# Shield_Amir_EDO_V_0_1.net
KiCad netlist of a schematic drawn in EasyEDA
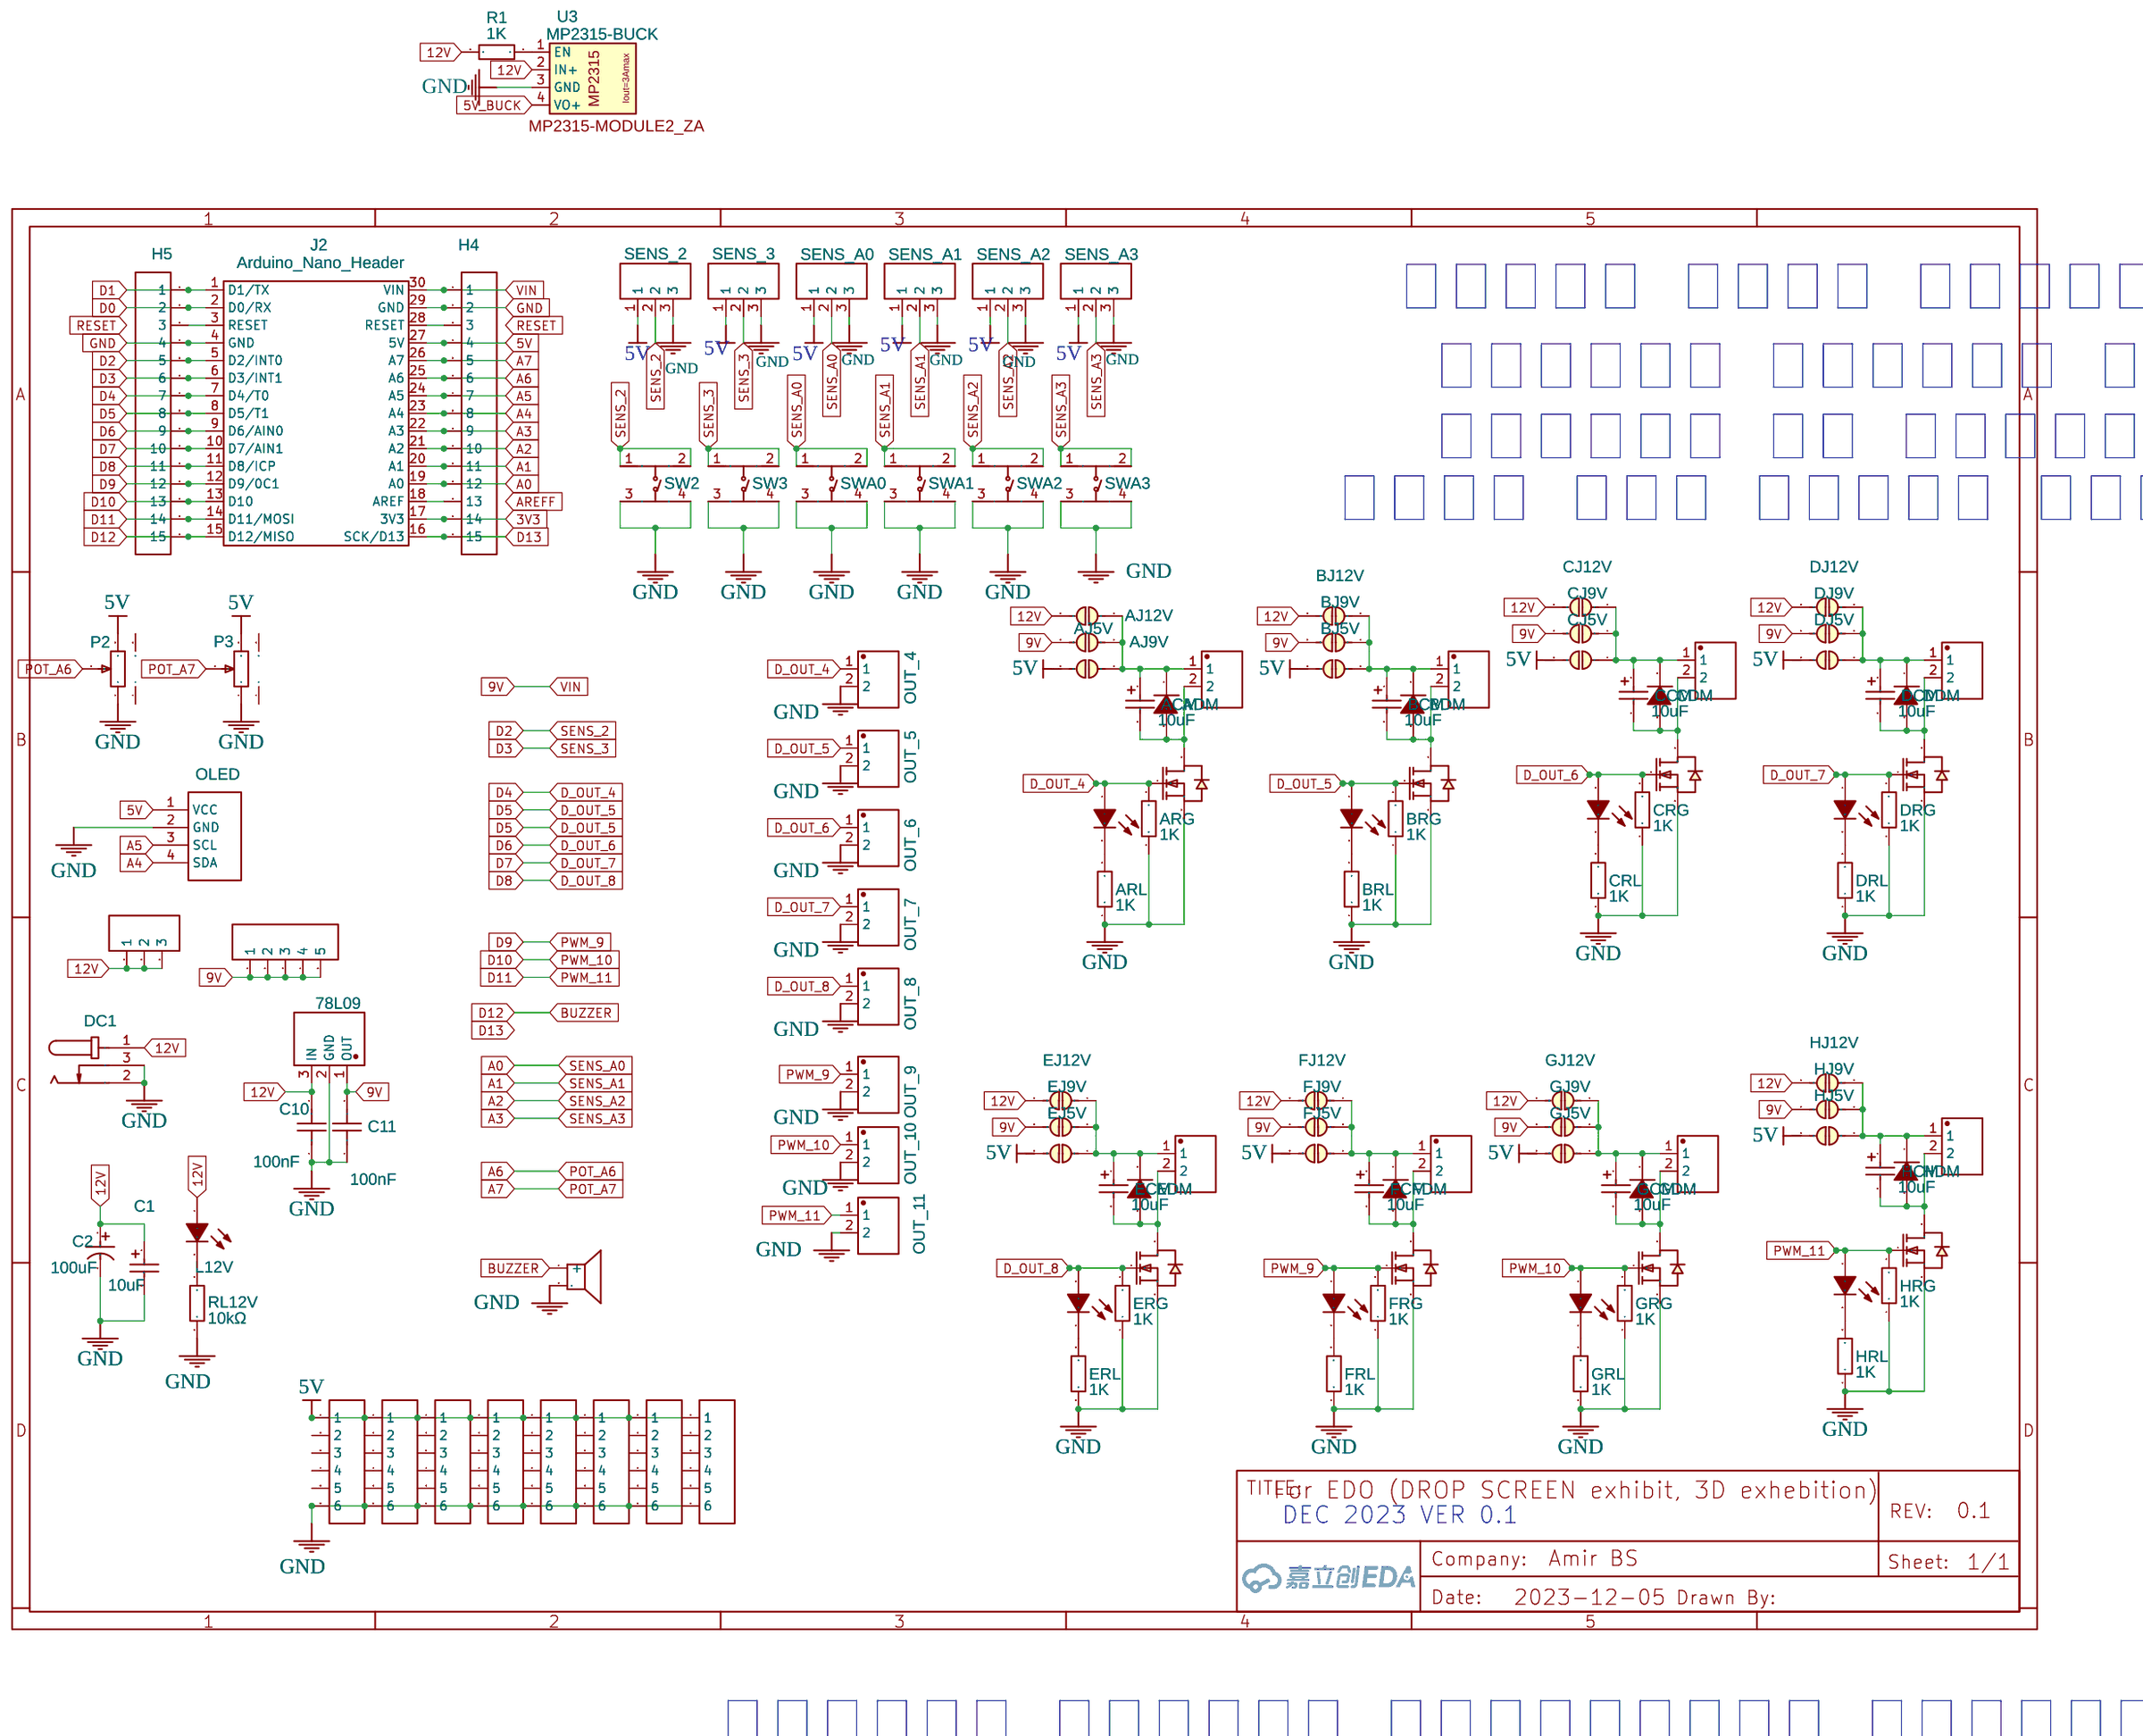
[diagram p0: schematic sheet]

(export (version "E")
  (design (tool "Eeschema 10.0.6"))
  (components
    (comp (ref "ACM")
      (value "10uF")
      (fields (field (name "Manufacturer Part") "TAJA106K016RNJ") (field (name "Manufacturer") "Kyocera AVX"))
      (libsource (lib "") (part "TAJA106K016RNJ_5"))
    )
    (comp (ref "ACON")
      (value "KF2510-2A")
      (fields (field (name "BOM_Supplier Part") "C27543"))
      (libsource (lib "") (part "KF2510-2A_8"))
    )
    (comp (ref "ADM")
      (value "1N4007")
      (fields (field (name "BOM_Manufacturer Part") "1N4007F") (field (name "BOM_Supplier Part") "C110856"))
      (libsource (lib "") (part "1N4007F_5"))
    )
    (comp (ref "AJ5V") (value "JUMPER-SMT_2") (libsource (lib "") (part "JUMPER-SMT_2_16")))
    (comp (ref "AJ9V") (value "JUMPER-SMT_2") (libsource (lib "") (part "JUMPER-SMT_2_12")))
    (comp (ref "AJ12V") (value "JUMPER-SMT_2") (libsource (lib "") (part "JUMPER-SMT_2_10")))
    (comp (ref "ALD")
      (value "LED")
      (fields
        (field (name "BOM_Manufacturer Part") "19-217/BHC-ZL1M2RY/3T")
        (field (name "BOM_Supplier Part") "C72041")
      )
      (libsource (lib "") (part "19-217/BHC-ZL1M2RY/3T_3"))
    )
    (comp (ref "AQ")
      (value "Q")
      (fields (field (name "BOM_Manufacturer Part") "AO3400") (field (name "BOM_Supplier Part") "C5224189"))
      (libsource (lib "") (part "JSM2302"))
    )
    (comp (ref "ARG")
      (value "1K")
      (fields
        (field (name "BOM_Manufacturer Part") "0603WAF1001T5E")
        (field (name "BOM_Supplier Part") "C21190")
      )
      (libsource (lib "") (part "0603WAF1001T5E_10"))
    )
    (comp (ref "ARL")
      (value "1K")
      (fields
        (field (name "BOM_Manufacturer Part") "0603WAF1001T5E")
        (field (name "BOM_Supplier Part") "C21190")
      )
      (libsource (lib "") (part "0603WAF1001T5E_4"))
    )
    (comp (ref "BCM")
      (value "10uF")
      (fields (field (name "Manufacturer Part") "TAJA106K016RNJ") (field (name "Manufacturer") "Kyocera AVX"))
      (libsource (lib "") (part "TAJA106K016RNJ_6"))
    )
    (comp (ref "BCON")
      (value "KF2510-2A")
      (fields (field (name "BOM_Supplier Part") "C27543"))
      (libsource (lib "") (part "KF2510-2A_7"))
    )
    (comp (ref "BDM")
      (value "1N4007")
      (fields (field (name "BOM_Manufacturer Part") "1N4007F") (field (name "BOM_Supplier Part") "C110856"))
      (libsource (lib "") (part "1N4007F"))
    )
    (comp (ref "BJ5V") (value "JUMPER-SMT_2") (libsource (lib "") (part "JUMPER-SMT_2_3")))
    (comp (ref "BJ9V") (value "JUMPER-SMT_2") (libsource (lib "") (part "JUMPER-SMT_2")))
    (comp (ref "BJ12V") (value "JUMPER-SMT_2") (libsource (lib "") (part "JUMPER-SMT_2_7")))
    (comp (ref "BLD")
      (value "LED")
      (fields
        (field (name "BOM_Manufacturer Part") "19-217/BHC-ZL1M2RY/3T")
        (field (name "BOM_Supplier Part") "C72041")
      )
      (libsource (lib "") (part "19-217/BHC-ZL1M2RY/3T_1"))
    )
    (comp (ref "BQ")
      (value "Q")
      (fields (field (name "BOM_Manufacturer Part") "AO3400") (field (name "BOM_Supplier Part") "C5224189"))
      (libsource (lib "") (part "JSM2302_4"))
    )
    (comp (ref "BRG")
      (value "1K")
      (fields
        (field (name "BOM_Manufacturer Part") "0603WAF1001T5E")
        (field (name "BOM_Supplier Part") "C21190")
      )
      (libsource (lib "") (part "0603WAF1001T5E_2"))
    )
    (comp (ref "BRL")
      (value "1K")
      (fields
        (field (name "BOM_Manufacturer Part") "0603WAF1001T5E")
        (field (name "BOM_Supplier Part") "C21190")
      )
      (libsource (lib "") (part "0603WAF1001T5E_13"))
    )
    (comp (ref "BUZZER1")
      (value "BUZZER-12X9")
      (fields (field (name "Manufacturer Part") "buzzer-12X9"))
      (libsource (lib "") (part "BUZZER-12X9"))
    )
    (comp (ref "C1")
      (value "10uF")
      (fields (field (name "Manufacturer Part") "TAJA106K016RNJ") (field (name "Manufacturer") "Kyocera AVX"))
      (libsource (lib "") (part "TAJA106K016RNJ_8"))
    )
    (comp (ref "C2")
      (value "100uF")
      (fields
        (field (name "Manufacturer Part") "KM107M035E11RR0VH2FP0")
        (field (name "Manufacturer") "CX(承兴)")
      )
      (libsource (lib "") (part "100uF 35V 6.3*11"))
    )
    (comp (ref "C10")
      (value "100nF")
      (fields
        (field (name "Manufacturer Part") "CC0603KRX7R9BB104")
        (field (name "Manufacturer") "YAGEO(国巨)")
      )
      (libsource (lib "") (part "CC0603KRX7R9BB104"))
    )
    (comp (ref "C11")
      (value "100nF")
      (fields
        (field (name "Manufacturer Part") "CC0603KRX7R9BB104")
        (field (name "Manufacturer") "YAGEO(国巨)")
      )
      (libsource (lib "") (part "CC0603KRX7R9BB104"))
    )
    (comp (ref "CCM")
      (value "10uF")
      (fields (field (name "Manufacturer Part") "TAJA106K016RNJ") (field (name "Manufacturer") "Kyocera AVX"))
      (libsource (lib "") (part "TAJA106K016RNJ_4"))
    )
    (comp (ref "CCON")
      (value "KF2510-2A")
      (fields (field (name "BOM_Supplier Part") "C27543"))
      (libsource (lib "") (part "KF2510-2A_3"))
    )
    (comp (ref "CDM")
      (value "1N4007")
      (fields (field (name "BOM_Manufacturer Part") "1N4007F") (field (name "BOM_Supplier Part") "C110856"))
      (libsource (lib "") (part "1N4007F_2"))
    )
    (comp (ref "CJ5V") (value "JUMPER-SMT_2") (libsource (lib "") (part "JUMPER-SMT_2_23")))
    (comp (ref "CJ9V") (value "JUMPER-SMT_2") (libsource (lib "") (part "JUMPER-SMT_2_20")))
    (comp (ref "CJ12V") (value "JUMPER-SMT_2") (libsource (lib "") (part "JUMPER-SMT_2_6")))
    (comp (ref "CLD")
      (value "LED")
      (fields
        (field (name "BOM_Manufacturer Part") "19-217/BHC-ZL1M2RY/3T")
        (field (name "BOM_Supplier Part") "C72041")
      )
      (libsource (lib "") (part "19-217/BHC-ZL1M2RY/3T_4"))
    )
    (comp (ref "CQ")
      (value "Q")
      (fields (field (name "BOM_Manufacturer Part") "AO3400") (field (name "BOM_Supplier Part") "C5224189"))
      (libsource (lib "") (part "JSM2302_3"))
    )
    (comp (ref "CRG")
      (value "1K")
      (fields
        (field (name "BOM_Manufacturer Part") "0603WAF1001T5E")
        (field (name "BOM_Supplier Part") "C21190")
      )
      (libsource (lib "") (part "0603WAF1001T5E_14"))
    )
    (comp (ref "CRL")
      (value "1K")
      (fields
        (field (name "BOM_Manufacturer Part") "0603WAF1001T5E")
        (field (name "BOM_Supplier Part") "C21190")
      )
      (libsource (lib "") (part "0603WAF1001T5E_16"))
    )
    (comp (ref "DC1")
      (value "DC")
      (fields
        (field (name "BOM_Manufacturer Part") "DC005-2.0MM")
        (field (name "BOM_Supplier Part") "C111567")
      )
      (libsource (lib "") (part "DC005-2.0MM"))
    )
    (comp (ref "DCM")
      (value "10uF")
      (fields (field (name "Manufacturer Part") "TAJA106K016RNJ") (field (name "Manufacturer") "Kyocera AVX"))
      (libsource (lib "") (part "TAJA106K016RNJ_7"))
    )
    (comp (ref "DCON")
      (value "KF2510-2A")
      (fields (field (name "BOM_Supplier Part") "C27543"))
      (libsource (lib "") (part "KF2510-2A_4"))
    )
    (comp (ref "DDM")
      (value "1N4007")
      (fields (field (name "BOM_Manufacturer Part") "1N4007F") (field (name "BOM_Supplier Part") "C110856"))
      (libsource (lib "") (part "1N4007F_7"))
    )
    (comp (ref "DJ5V") (value "JUMPER-SMT_2") (libsource (lib "") (part "JUMPER-SMT_2_21")))
    (comp (ref "DJ9V") (value "JUMPER-SMT_2") (libsource (lib "") (part "JUMPER-SMT_2_4")))
    (comp (ref "DJ12V") (value "JUMPER-SMT_2") (libsource (lib "") (part "JUMPER-SMT_2_5")))
    (comp (ref "DLD")
      (value "LED")
      (fields
        (field (name "BOM_Manufacturer Part") "19-217/BHC-ZL1M2RY/3T")
        (field (name "BOM_Supplier Part") "C72041")
      )
      (libsource (lib "") (part "19-217/BHC-ZL1M2RY/3T_7"))
    )
    (comp (ref "DQ")
      (value "Q")
      (fields (field (name "BOM_Manufacturer Part") "AO3400") (field (name "BOM_Supplier Part") "C5224189"))
      (libsource (lib "") (part "JSM2302_6"))
    )
    (comp (ref "DRG")
      (value "1K")
      (fields
        (field (name "BOM_Manufacturer Part") "0603WAF1001T5E")
        (field (name "BOM_Supplier Part") "C21190")
      )
      (libsource (lib "") (part "0603WAF1001T5E_15"))
    )
    (comp (ref "DRL")
      (value "1K")
      (fields
        (field (name "BOM_Manufacturer Part") "0603WAF1001T5E")
        (field (name "BOM_Supplier Part") "C21190")
      )
      (libsource (lib "") (part "0603WAF1001T5E_12"))
    )
    (comp (ref "ECM")
      (value "10uF")
      (fields (field (name "Manufacturer Part") "TAJA106K016RNJ") (field (name "Manufacturer") "Kyocera AVX"))
      (libsource (lib "") (part "TAJA106K016RNJ_3"))
    )
    (comp (ref "ECON")
      (value "KF2510-2A")
      (fields (field (name "BOM_Supplier Part") "C27543"))
      (libsource (lib "") (part "KF2510-2A_2"))
    )
    (comp (ref "EDM")
      (value "1N4007")
      (fields (field (name "BOM_Manufacturer Part") "1N4007F") (field (name "BOM_Supplier Part") "C110856"))
      (libsource (lib "") (part "1N4007F_6"))
    )
    (comp (ref "EJ5V") (value "JUMPER-SMT_2") (libsource (lib "") (part "JUMPER-SMT_2_9")))
    (comp (ref "EJ9V") (value "JUMPER-SMT_2") (libsource (lib "") (part "JUMPER-SMT_2_11")))
    (comp (ref "EJ12V") (value "JUMPER-SMT_2") (libsource (lib "") (part "JUMPER-SMT_2_15")))
    (comp (ref "ELD")
      (value "LED")
      (fields
        (field (name "BOM_Manufacturer Part") "19-217/BHC-ZL1M2RY/3T")
        (field (name "BOM_Supplier Part") "C72041")
      )
      (libsource (lib "") (part "19-217/BHC-ZL1M2RY/3T"))
    )
    (comp (ref "EQ")
      (value "Q")
      (fields (field (name "BOM_Manufacturer Part") "AO3400") (field (name "BOM_Supplier Part") "C5224189"))
      (libsource (lib "") (part "JSM2302_2"))
    )
    (comp (ref "ERG")
      (value "1K")
      (fields
        (field (name "BOM_Manufacturer Part") "0603WAF1001T5E")
        (field (name "BOM_Supplier Part") "C21190")
      )
      (libsource (lib "") (part "0603WAF1001T5E_3"))
    )
    (comp (ref "ERL")
      (value "1K")
      (fields
        (field (name "BOM_Manufacturer Part") "0603WAF1001T5E")
        (field (name "BOM_Supplier Part") "C21190")
      )
      (libsource (lib "") (part "0603WAF1001T5E_8"))
    )
    (comp (ref "FCM")
      (value "10uF")
      (fields (field (name "Manufacturer Part") "TAJA106K016RNJ") (field (name "Manufacturer") "Kyocera AVX"))
      (libsource (lib "") (part "TAJA106K016RNJ_1"))
    )
    (comp (ref "FCON")
      (value "KF2510-2A")
      (fields (field (name "BOM_Supplier Part") "C27543"))
      (libsource (lib "") (part "KF2510-2A"))
    )
    (comp (ref "FDM")
      (value "1N4007")
      (fields (field (name "BOM_Manufacturer Part") "1N4007F") (field (name "BOM_Supplier Part") "C110856"))
      (libsource (lib "") (part "1N4007F_1"))
    )
    (comp (ref "FJ5V") (value "JUMPER-SMT_2") (libsource (lib "") (part "JUMPER-SMT_2_17")))
    (comp (ref "FJ9V") (value "JUMPER-SMT_2") (libsource (lib "") (part "JUMPER-SMT_2_14")))
    (comp (ref "FJ12V") (value "JUMPER-SMT_2") (libsource (lib "") (part "JUMPER-SMT_2_18")))
    (comp (ref "FLD")
      (value "LED")
      (fields
        (field (name "BOM_Manufacturer Part") "19-217/BHC-ZL1M2RY/3T")
        (field (name "BOM_Supplier Part") "C72041")
      )
      (libsource (lib "") (part "19-217/BHC-ZL1M2RY/3T_2"))
    )
    (comp (ref "FQ")
      (value "Q")
      (fields (field (name "BOM_Manufacturer Part") "AO3400") (field (name "BOM_Supplier Part") "C5224189"))
      (libsource (lib "") (part "JSM2302_7"))
    )
    (comp (ref "FRG")
      (value "1K")
      (fields
        (field (name "BOM_Manufacturer Part") "0603WAF1001T5E")
        (field (name "BOM_Supplier Part") "C21190")
      )
      (libsource (lib "") (part "0603WAF1001T5E_11"))
    )
    (comp (ref "FRL")
      (value "1K")
      (fields
        (field (name "BOM_Manufacturer Part") "0603WAF1001T5E")
        (field (name "BOM_Supplier Part") "C21190")
      )
      (libsource (lib "") (part "0603WAF1001T5E_9"))
    )
    (comp (ref "GCM")
      (value "10uF")
      (fields (field (name "Manufacturer Part") "TAJA106K016RNJ") (field (name "Manufacturer") "Kyocera AVX"))
      (libsource (lib "") (part "TAJA106K016RNJ"))
    )
    (comp (ref "GCON")
      (value "KF2510-2A")
      (fields (field (name "BOM_Supplier Part") "C27543"))
      (libsource (lib "") (part "KF2510-2A_5"))
    )
    (comp (ref "GDM")
      (value "1N4007")
      (fields (field (name "BOM_Manufacturer Part") "1N4007F") (field (name "BOM_Supplier Part") "C110856"))
      (libsource (lib "") (part "1N4007F_4"))
    )
    (comp (ref "GJ5V") (value "JUMPER-SMT_2") (libsource (lib "") (part "JUMPER-SMT_2_19")))
    (comp (ref "GJ9V") (value "JUMPER-SMT_2") (libsource (lib "") (part "JUMPER-SMT_2_22")))
    (comp (ref "GJ12V") (value "JUMPER-SMT_2") (libsource (lib "") (part "JUMPER-SMT_2_1")))
    (comp (ref "GLD")
      (value "LED")
      (fields
        (field (name "BOM_Manufacturer Part") "19-217/BHC-ZL1M2RY/3T")
        (field (name "BOM_Supplier Part") "C72041")
      )
      (libsource (lib "") (part "19-217/BHC-ZL1M2RY/3T_8"))
    )
    (comp (ref "GQ")
      (value "Q")
      (fields (field (name "BOM_Manufacturer Part") "AO3400") (field (name "BOM_Supplier Part") "C5224189"))
      (libsource (lib "") (part "JSM2302_1"))
    )
    (comp (ref "GRG")
      (value "1K")
      (fields
        (field (name "BOM_Manufacturer Part") "0603WAF1001T5E")
        (field (name "BOM_Supplier Part") "C21190")
      )
      (libsource (lib "") (part "0603WAF1001T5E_7"))
    )
    (comp (ref "GRL")
      (value "1K")
      (fields
        (field (name "BOM_Manufacturer Part") "0603WAF1001T5E")
        (field (name "BOM_Supplier Part") "C21190")
      )
      (libsource (lib "") (part "0603WAF1001T5E_6"))
    )
    (comp (ref "H1")
      (value "HDR-F-2.54_1x6")
      (fields (field (name "BOM_Supplier Part") "C40877"))
      (libsource (lib "") (part "HDR-F-2.54_1x6"))
    )
    (comp (ref "H2")
      (value "HDR-F-2.54_1x6")
      (fields (field (name "BOM_Supplier Part") "C40877"))
      (libsource (lib "") (part "HDR-F-2.54_1x6"))
    )
    (comp (ref "H3")
      (value "HDR-F-2.54_1x6")
      (fields (field (name "BOM_Supplier Part") "C40877"))
      (libsource (lib "") (part "HDR-F-2.54_1x6"))
    )
    (comp (ref "H4")
      (value "HDR-F-2.54_1x15")
      (fields (field (name "BOM_Supplier Part") "C124408"))
      (libsource (lib "") (part "HDR-F-2.54_1x15_1"))
    )
    (comp (ref "H5")
      (value "HDR-F-2.54_1x15")
      (fields (field (name "BOM_Supplier Part") "C124408"))
      (libsource (lib "") (part "HDR-F-2.54_1x15"))
    )
    (comp (ref "H6")
      (value "HDR-F-2.54_1x6")
      (fields (field (name "BOM_Supplier Part") "C40877"))
      (libsource (lib "") (part "HDR-F-2.54_1x6"))
    )
    (comp (ref "H8")
      (value "HDR-F-2.54_1x6")
      (fields (field (name "BOM_Supplier Part") "C40877"))
      (libsource (lib "") (part "HDR-F-2.54_1x6"))
    )
    (comp (ref "H9")
      (value "HDR-F-2.54_1x6")
      (fields (field (name "BOM_Supplier Part") "C40877"))
      (libsource (lib "") (part "HDR-F-2.54_1x6"))
    )
    (comp (ref "H9V")
      (value "HDR-F-2.54_1x5")
      (fields (field (name "BOM_Supplier Part") "C50950"))
      (libsource (lib "") (part "HDR-F-2.54_1x5"))
    )
    (comp (ref "H10")
      (value "HDR-F-2.54_1x6")
      (fields (field (name "BOM_Supplier Part") "C40877"))
      (libsource (lib "") (part "HDR-F-2.54_1x6"))
    )
    (comp (ref "H11")
      (value "HDR-F-2.54_1x6")
      (fields (field (name "BOM_Supplier Part") "C40877"))
      (libsource (lib "") (part "HDR-F-2.54_1x6"))
    )
    (comp (ref "H12V")
      (value "HDR-F-2.54_1x3")
      (fields (field (name "BOM_Supplier Part") "C146690"))
      (libsource (lib "") (part "HDR-F-2.54_1x3"))
    )
    (comp (ref "HCM")
      (value "10uF")
      (fields (field (name "Manufacturer Part") "TAJA106K016RNJ") (field (name "Manufacturer") "Kyocera AVX"))
      (libsource (lib "") (part "TAJA106K016RNJ_2"))
    )
    (comp (ref "HCON")
      (value "KF2510-2A")
      (fields (field (name "BOM_Supplier Part") "C27543"))
      (libsource (lib "") (part "KF2510-2A_6"))
    )
    (comp (ref "HDM")
      (value "1N4007")
      (fields (field (name "BOM_Manufacturer Part") "1N4007F") (field (name "BOM_Supplier Part") "C110856"))
      (libsource (lib "") (part "1N4007F_3"))
    )
    (comp (ref "HJ5V") (value "JUMPER-SMT_2") (libsource (lib "") (part "JUMPER-SMT_2_8")))
    (comp (ref "HJ9V") (value "JUMPER-SMT_2") (libsource (lib "") (part "JUMPER-SMT_2_2")))
    (comp (ref "HJ12V") (value "JUMPER-SMT_2") (libsource (lib "") (part "JUMPER-SMT_2_13")))
    (comp (ref "HLD")
      (value "LED")
      (fields
        (field (name "BOM_Manufacturer Part") "19-217/BHC-ZL1M2RY/3T")
        (field (name "BOM_Supplier Part") "C72041")
      )
      (libsource (lib "") (part "19-217/BHC-ZL1M2RY/3T_5"))
    )
    (comp (ref "HQ")
      (value "Q")
      (fields (field (name "BOM_Manufacturer Part") "AO3400") (field (name "BOM_Supplier Part") "C5224189"))
      (libsource (lib "") (part "JSM2302_5"))
    )
    (comp (ref "HRG")
      (value "1K")
      (fields
        (field (name "BOM_Manufacturer Part") "0603WAF1001T5E")
        (field (name "BOM_Supplier Part") "C21190")
      )
      (libsource (lib "") (part "0603WAF1001T5E"))
    )
    (comp (ref "HRL")
      (value "1K")
      (fields
        (field (name "BOM_Manufacturer Part") "0603WAF1001T5E")
        (field (name "BOM_Supplier Part") "C21190")
      )
      (libsource (lib "") (part "0603WAF1001T5E_1"))
    )
    (comp (ref "J2") (value "Arduino_Nano_Header") (libsource (lib "") (part "Arduino_Nano_Header")))
    (comp (ref "L12V")
      (value "LED")
      (fields
        (field (name "BOM_Manufacturer Part") "19-217/BHC-ZL1M2RY/3T")
        (field (name "BOM_Supplier Part") "C72041")
      )
      (libsource (lib "") (part "19-217/BHC-ZL1M2RY/3T_6"))
    )
    (comp (ref "OLED")
      (value "1.3 inch OLED SSH1106 I2C 128x64 copy")
      (libsource (lib "") (part "1.3 inch OLED SSH1106 I2C 128x64 copy"))
    )
    (comp (ref "OUT_4")
      (value "KF2510-2A")
      (fields (field (name "BOM_Supplier Part") "C27543"))
      (libsource (lib "") (part "KF2510-2A_1"))
    )
    (comp (ref "OUT_5")
      (value "KF2510-2A")
      (fields (field (name "BOM_Supplier Part") "C27543"))
      (libsource (lib "") (part "KF2510-2A_1"))
    )
    (comp (ref "OUT_6")
      (value "KF2510-2A")
      (fields (field (name "BOM_Supplier Part") "C27543"))
      (libsource (lib "") (part "KF2510-2A_1"))
    )
    (comp (ref "OUT_7")
      (value "KF2510-2A")
      (fields (field (name "BOM_Supplier Part") "C27543"))
      (libsource (lib "") (part "KF2510-2A_1"))
    )
    (comp (ref "OUT_8")
      (value "KF2510-2A")
      (fields (field (name "BOM_Supplier Part") "C27543"))
      (libsource (lib "") (part "KF2510-2A_1"))
    )
    (comp (ref "OUT_9")
      (value "KF2510-2A")
      (fields (field (name "BOM_Supplier Part") "C27543"))
      (libsource (lib "") (part "KF2510-2A_1"))
    )
    (comp (ref "OUT_10")
      (value "KF2510-2A")
      (fields (field (name "BOM_Supplier Part") "C27543"))
      (libsource (lib "") (part "KF2510-2A_1"))
    )
    (comp (ref "OUT_11")
      (value "KF2510-2A")
      (fields (field (name "BOM_Supplier Part") "C27543"))
      (libsource (lib "") (part "KF2510-2A_1"))
    )
    (comp (ref "P2")
      (value "长柄旋转电位器")
      (fields (field (name "BOM_Supplier Part") "C2874842"))
      (libsource (lib "") (part "长柄旋转电位器"))
    )
    (comp (ref "P3")
      (value "长柄旋转电位器")
      (fields (field (name "BOM_Supplier Part") "C2874842"))
      (libsource (lib "") (part "长柄旋转电位器"))
    )
    (comp (ref "R1")
      (value "1K")
      (fields
        (field (name "BOM_Manufacturer Part") "0603WAF1001T5E")
        (field (name "BOM_Supplier Part") "C21190")
      )
      (libsource (lib "") (part "0603WAF1001T5E_5"))
    )
    (comp (ref "RL12V")
      (value "10kΩ")
      (fields
        (field (name "BOM_Manufacturer Part") "0603WAF1002T5E")
        (field (name "BOM_Supplier Part") "C25804")
      )
      (libsource (lib "") (part "0603WAF1002T5E"))
    )
    (comp (ref "SENS_2")
      (value "FK2510")
      (fields (field (name "Manufacturer Part") "2510-3A") (field (name "Manufacturer") "BOOMELE(博穆精密)"))
      (libsource (lib "") (part "kf2510_3A"))
    )
    (comp (ref "SENS_3")
      (value "FK2510")
      (fields (field (name "Manufacturer Part") "2510-3A") (field (name "Manufacturer") "BOOMELE(博穆精密)"))
      (libsource (lib "") (part "kf2510_3A"))
    )
    (comp (ref "SENS_A0")
      (value "FK2510")
      (fields (field (name "Manufacturer Part") "2510-3A") (field (name "Manufacturer") "BOOMELE(博穆精密)"))
      (libsource (lib "") (part "kf2510_3A_1"))
    )
    (comp (ref "SENS_A1")
      (value "FK2510")
      (fields (field (name "Manufacturer Part") "2510-3A") (field (name "Manufacturer") "BOOMELE(博穆精密)"))
      (libsource (lib "") (part "kf2510_3A_1"))
    )
    (comp (ref "SENS_A2")
      (value "FK2510")
      (fields (field (name "Manufacturer Part") "2510-3A") (field (name "Manufacturer") "BOOMELE(博穆精密)"))
      (libsource (lib "") (part "kf2510_3A_1"))
    )
    (comp (ref "SENS_A3")
      (value "FK2510")
      (fields (field (name "Manufacturer Part") "2510-3A") (field (name "Manufacturer") "BOOMELE(博穆精密)"))
      (libsource (lib "") (part "kf2510_3A_1"))
    )
    (comp (ref "SW2")
      (value "TC-6610-7-160G")
      (fields (field (name "Manufacturer") "HCTL(华灿天禄)"))
      (libsource (lib "") (part "TC-6610-7-160G_1"))
    )
    (comp (ref "SW3")
      (value "TC-6610-7-160G")
      (fields (field (name "Manufacturer") "HCTL(华灿天禄)"))
      (libsource (lib "") (part "TC-6610-7-160G_1"))
    )
    (comp (ref "SWA0")
      (value "TC-6610-7-160G")
      (fields (field (name "Manufacturer") "HCTL(华灿天禄)"))
      (libsource (lib "") (part "TC-6610-7-160G"))
    )
    (comp (ref "SWA1")
      (value "TC-6610-7-160G")
      (fields (field (name "Manufacturer") "HCTL(华灿天禄)"))
      (libsource (lib "") (part "TC-6610-7-160G"))
    )
    (comp (ref "SWA2")
      (value "TC-6610-7-160G")
      (fields (field (name "Manufacturer") "HCTL(华灿天禄)"))
      (libsource (lib "") (part "TC-6610-7-160G"))
    )
    (comp (ref "SWA3")
      (value "TC-6610-7-160G")
      (fields (field (name "Manufacturer") "HCTL(华灿天禄)"))
      (libsource (lib "") (part "TC-6610-7-160G"))
    )
    (comp (ref "U3") (value "MP2315-BUCK") (libsource (lib "") (part "MP2315-BUCK")))
    (comp (ref "U5")
      (value "78L09")
      (fields (field (name "Manufacturer Part") "78L09U 78L09") (field (name "Manufacturer") "CBI(创基)"))
      (libsource (lib "") (part "78L09U 78L09"))
    )
  )
  (nets
    (net (code "1") (name "3V3") (class "Default")
      (node (ref "H4") (pin "14") (pinfunction "14_14") (pintype "unspecified"))
      (node (ref "J2") (pin "17") (pinfunction "3V3_17") (pintype "unspecified"))
    )
    (net (code "2") (name "5V") (class "Default")
      (node (ref "AJ5V") (pin "2") (pinfunction "2_2") (pintype "bidirectional"))
      (node (ref "BJ5V") (pin "2") (pinfunction "2_2") (pintype "bidirectional"))
      (node (ref "CJ5V") (pin "2") (pinfunction "2_2") (pintype "bidirectional"))
      (node (ref "DJ5V") (pin "2") (pinfunction "2_2") (pintype "bidirectional"))
      (node (ref "EJ5V") (pin "2") (pinfunction "2_2") (pintype "bidirectional"))
      (node (ref "FJ5V") (pin "2") (pinfunction "2_2") (pintype "bidirectional"))
      (node (ref "GJ5V") (pin "2") (pinfunction "2_2") (pintype "bidirectional"))
      (node (ref "H1") (pin "1") (pinfunction "1_1") (pintype "input"))
      (node (ref "H10") (pin "1") (pinfunction "1_1") (pintype "input"))
      (node (ref "H11") (pin "1") (pinfunction "1_1") (pintype "input"))
      (node (ref "H2") (pin "1") (pinfunction "1_1") (pintype "input"))
      (node (ref "H3") (pin "1") (pinfunction "1_1") (pintype "input"))
      (node (ref "H4") (pin "4") (pinfunction "4_4") (pintype "unspecified"))
      (node (ref "H6") (pin "1") (pinfunction "1_1") (pintype "input"))
      (node (ref "H8") (pin "1") (pinfunction "1_1") (pintype "input"))
      (node (ref "H9") (pin "1") (pinfunction "1_1") (pintype "input"))
      (node (ref "HJ5V") (pin "2") (pinfunction "2_2") (pintype "bidirectional"))
      (node (ref "J2") (pin "27") (pinfunction "5V_27") (pintype "unspecified"))
      (node (ref "OLED") (pin "1") (pinfunction "VCC_1") (pintype "passive"))
      (node (ref "P2") (pin "3") (pinfunction "3_3") (pintype "input"))
      (node (ref "P3") (pin "3") (pinfunction "3_3") (pintype "input"))
      (node (ref "SENS_2") (pin "1") (pinfunction "1_1") (pintype "unspecified"))
      (node (ref "SENS_3") (pin "1") (pinfunction "1_1") (pintype "unspecified"))
      (node (ref "SENS_A0") (pin "1") (pinfunction "1_1") (pintype "unspecified"))
      (node (ref "SENS_A1") (pin "1") (pinfunction "1_1") (pintype "unspecified"))
      (node (ref "SENS_A2") (pin "1") (pinfunction "1_1") (pintype "unspecified"))
      (node (ref "SENS_A3") (pin "1") (pinfunction "1_1") (pintype "unspecified"))
    )
    (net (code "3") (name "5V_BUCK") (class "Default")
      (node (ref "U3") (pin "4") (pinfunction "VO+_4") (pintype "unspecified"))
    )
    (net (code "4") (name "9V") (class "Default")
      (node (ref "AJ9V") (pin "2") (pinfunction "2_2") (pintype "bidirectional"))
      (node (ref "BJ9V") (pin "2") (pinfunction "2_2") (pintype "bidirectional"))
      (node (ref "C11") (pin "2") (pinfunction "2_2") (pintype "unspecified"))
      (node (ref "CJ9V") (pin "2") (pinfunction "2_2") (pintype "bidirectional"))
      (node (ref "DJ9V") (pin "2") (pinfunction "2_2") (pintype "bidirectional"))
      (node (ref "EJ9V") (pin "2") (pinfunction "2_2") (pintype "bidirectional"))
      (node (ref "FJ9V") (pin "2") (pinfunction "2_2") (pintype "bidirectional"))
      (node (ref "GJ9V") (pin "2") (pinfunction "2_2") (pintype "bidirectional"))
      (node (ref "H4") (pin "1") (pinfunction "1_1") (pintype "unspecified"))
      (node (ref "H9V") (pin "1") (pinfunction "1_1") (pintype "unspecified"))
      (node (ref "H9V") (pin "2") (pinfunction "2_2") (pintype "unspecified"))
      (node (ref "H9V") (pin "3") (pinfunction "3_3") (pintype "unspecified"))
      (node (ref "H9V") (pin "4") (pinfunction "4_4") (pintype "unspecified"))
      (node (ref "H9V") (pin "5") (pinfunction "5_5") (pintype "unspecified"))
      (node (ref "HJ9V") (pin "2") (pinfunction "2_2") (pintype "bidirectional"))
      (node (ref "J2") (pin "30") (pinfunction "VIN_30") (pintype "unspecified"))
      (node (ref "U5") (pin "1") (pinfunction "OUT_1") (pintype "unspecified"))
    )
    (net (code "5") (name "12V") (class "Default")
      (node (ref "AJ12V") (pin "2") (pinfunction "2_2") (pintype "bidirectional"))
      (node (ref "BJ12V") (pin "2") (pinfunction "2_2") (pintype "bidirectional"))
      (node (ref "C1") (pin "1") (pinfunction "1_1") (pintype "input"))
      (node (ref "C10") (pin "2") (pinfunction "2_2") (pintype "unspecified"))
      (node (ref "C2") (pin "1") (pinfunction "1_1") (pintype "input"))
      (node (ref "CJ12V") (pin "2") (pinfunction "2_2") (pintype "bidirectional"))
      (node (ref "DC1") (pin "1") (pinfunction "1_1") (pintype "unspecified"))
      (node (ref "DJ12V") (pin "2") (pinfunction "2_2") (pintype "bidirectional"))
      (node (ref "EJ12V") (pin "2") (pinfunction "2_2") (pintype "bidirectional"))
      (node (ref "FJ12V") (pin "2") (pinfunction "2_2") (pintype "bidirectional"))
      (node (ref "GJ12V") (pin "2") (pinfunction "2_2") (pintype "bidirectional"))
      (node (ref "H12V") (pin "1") (pinfunction "1_1") (pintype "input"))
      (node (ref "H12V") (pin "2") (pinfunction "2_2") (pintype "input"))
      (node (ref "H12V") (pin "3") (pinfunction "3_3") (pintype "input"))
      (node (ref "HJ12V") (pin "2") (pinfunction "2_2") (pintype "bidirectional"))
      (node (ref "L12V") (pin "1") (pinfunction "A_1") (pintype "input"))
      (node (ref "R1") (pin "2") (pinfunction "2_2") (pintype "input"))
      (node (ref "U3") (pin "2") (pinfunction "IN+_2") (pintype "unspecified"))
      (node (ref "U5") (pin "3") (pinfunction "IN_3") (pintype "unspecified"))
    )
    (net (code "6") (name "A0") (class "Default")
      (node (ref "H4") (pin "12") (pinfunction "12_12") (pintype "unspecified"))
      (node (ref "J2") (pin "19") (pinfunction "A0_19") (pintype "unspecified"))
      (node (ref "SENS_A0") (pin "2") (pinfunction "2_2") (pintype "unspecified"))
      (node (ref "SWA0") (pin "1") (pinfunction "1_1") (pintype "unspecified"))
      (node (ref "SWA0") (pin "2") (pinfunction "2_2") (pintype "unspecified"))
    )
    (net (code "7") (name "A1") (class "Default")
      (node (ref "H4") (pin "11") (pinfunction "11_11") (pintype "unspecified"))
      (node (ref "J2") (pin "20") (pinfunction "A1_20") (pintype "unspecified"))
      (node (ref "SENS_A1") (pin "2") (pinfunction "2_2") (pintype "unspecified"))
      (node (ref "SWA1") (pin "1") (pinfunction "1_1") (pintype "unspecified"))
      (node (ref "SWA1") (pin "2") (pinfunction "2_2") (pintype "unspecified"))
    )
    (net (code "8") (name "A2") (class "Default")
      (node (ref "H4") (pin "10") (pinfunction "10_10") (pintype "unspecified"))
      (node (ref "J2") (pin "21") (pinfunction "A2_21") (pintype "unspecified"))
      (node (ref "SENS_A2") (pin "2") (pinfunction "2_2") (pintype "unspecified"))
      (node (ref "SWA2") (pin "1") (pinfunction "1_1") (pintype "unspecified"))
      (node (ref "SWA2") (pin "2") (pinfunction "2_2") (pintype "unspecified"))
    )
    (net (code "9") (name "A3") (class "Default")
      (node (ref "H4") (pin "9") (pinfunction "9_9") (pintype "unspecified"))
      (node (ref "J2") (pin "22") (pinfunction "A3_22") (pintype "unspecified"))
      (node (ref "SENS_A3") (pin "2") (pinfunction "2_2") (pintype "unspecified"))
      (node (ref "SWA3") (pin "1") (pinfunction "1_1") (pintype "unspecified"))
      (node (ref "SWA3") (pin "2") (pinfunction "2_2") (pintype "unspecified"))
    )
    (net (code "10") (name "A4") (class "Default")
      (node (ref "H4") (pin "8") (pinfunction "8_8") (pintype "unspecified"))
      (node (ref "J2") (pin "23") (pinfunction "A4_23") (pintype "unspecified"))
      (node (ref "OLED") (pin "4") (pinfunction "SDA_4") (pintype "bidirectional"))
    )
    (net (code "11") (name "A5") (class "Default")
      (node (ref "H4") (pin "7") (pinfunction "7_7") (pintype "unspecified"))
      (node (ref "J2") (pin "24") (pinfunction "A5_24") (pintype "unspecified"))
      (node (ref "OLED") (pin "3") (pinfunction "SCL_3") (pintype "bidirectional"))
    )
    (net (code "12") (name "A6") (class "Default")
      (node (ref "H4") (pin "6") (pinfunction "6_6") (pintype "unspecified"))
      (node (ref "J2") (pin "25") (pinfunction "A6_25") (pintype "unspecified"))
      (node (ref "P2") (pin "2") (pinfunction "2_2") (pintype "input"))
    )
    (net (code "13") (name "A7") (class "Default")
      (node (ref "H4") (pin "5") (pinfunction "5_5") (pintype "unspecified"))
      (node (ref "J2") (pin "26") (pinfunction "A7_26") (pintype "unspecified"))
      (node (ref "P3") (pin "2") (pinfunction "2_2") (pintype "input"))
    )
    (net (code "15") (name "BUZZER") (class "Default")
      (node (ref "BUZZER1") (pin "1") (pinfunction "+_1") (pintype "unspecified"))
      (node (ref "H5") (pin "15") (pinfunction "15_15") (pintype "unspecified"))
      (node (ref "J2") (pin "15") (pinfunction "D12/MISO_15") (pintype "unspecified"))
    )
    (net (code "16") (name "D0") (class "Default")
      (node (ref "H5") (pin "2") (pinfunction "2_2") (pintype "unspecified"))
      (node (ref "J2") (pin "2") (pinfunction "D0/RX_2") (pintype "unspecified"))
    )
    (net (code "17") (name "D1") (class "Default")
      (node (ref "H5") (pin "1") (pinfunction "1_1") (pintype "unspecified"))
      (node (ref "J2") (pin "1") (pinfunction "D1/TX_1") (pintype "unspecified"))
    )
    (net (code "18") (name "D2") (class "Default")
      (node (ref "H5") (pin "5") (pinfunction "5_5") (pintype "unspecified"))
      (node (ref "J2") (pin "5") (pinfunction "D2/INT0_5") (pintype "unspecified"))
      (node (ref "SENS_2") (pin "2") (pinfunction "2_2") (pintype "unspecified"))
      (node (ref "SW2") (pin "1") (pinfunction "1_1") (pintype "unspecified"))
      (node (ref "SW2") (pin "2") (pinfunction "2_2") (pintype "unspecified"))
    )
    (net (code "19") (name "D3") (class "Default")
      (node (ref "H5") (pin "6") (pinfunction "6_6") (pintype "unspecified"))
      (node (ref "J2") (pin "6") (pinfunction "D3/INT1_6") (pintype "unspecified"))
      (node (ref "SENS_3") (pin "2") (pinfunction "2_2") (pintype "unspecified"))
      (node (ref "SW3") (pin "1") (pinfunction "1_1") (pintype "unspecified"))
      (node (ref "SW3") (pin "2") (pinfunction "2_2") (pintype "unspecified"))
    )
    (net (code "20") (name "D4") (class "Default")
      (node (ref "ALD") (pin "1") (pinfunction "A_1") (pintype "input"))
      (node (ref "AQ") (pin "1") (pinfunction "G_1") (pintype "unspecified"))
      (node (ref "ARG") (pin "2") (pinfunction "2_2") (pintype "input"))
      (node (ref "H5") (pin "7") (pinfunction "7_7") (pintype "unspecified"))
      (node (ref "J2") (pin "7") (pinfunction "D4/T0_7") (pintype "unspecified"))
      (node (ref "OUT_4") (pin "1") (pinfunction "1_1") (pintype "unspecified"))
    )
    (net (code "21") (name "D5") (class "Default")
      (node (ref "BLD") (pin "1") (pinfunction "A_1") (pintype "input"))
      (node (ref "BQ") (pin "1") (pinfunction "G_1") (pintype "unspecified"))
      (node (ref "BRG") (pin "2") (pinfunction "2_2") (pintype "input"))
      (node (ref "H5") (pin "8") (pinfunction "8_8") (pintype "unspecified"))
      (node (ref "J2") (pin "8") (pinfunction "D5/T1_8") (pintype "unspecified"))
      (node (ref "OUT_5") (pin "1") (pinfunction "1_1") (pintype "unspecified"))
    )
    (net (code "22") (name "D6") (class "Default")
      (node (ref "CLD") (pin "1") (pinfunction "A_1") (pintype "input"))
      (node (ref "CQ") (pin "1") (pinfunction "G_1") (pintype "unspecified"))
      (node (ref "CRG") (pin "2") (pinfunction "2_2") (pintype "input"))
      (node (ref "H5") (pin "9") (pinfunction "9_9") (pintype "unspecified"))
      (node (ref "J2") (pin "9") (pinfunction "D6/AIN0_9") (pintype "unspecified"))
      (node (ref "OUT_6") (pin "1") (pinfunction "1_1") (pintype "unspecified"))
    )
    (net (code "23") (name "D7") (class "Default")
      (node (ref "DLD") (pin "1") (pinfunction "A_1") (pintype "input"))
      (node (ref "DQ") (pin "1") (pinfunction "G_1") (pintype "unspecified"))
      (node (ref "DRG") (pin "2") (pinfunction "2_2") (pintype "input"))
      (node (ref "H5") (pin "10") (pinfunction "10_10") (pintype "unspecified"))
      (node (ref "J2") (pin "10") (pinfunction "D7/AIN1_10") (pintype "unspecified"))
      (node (ref "OUT_7") (pin "1") (pinfunction "1_1") (pintype "unspecified"))
    )
    (net (code "24") (name "D8") (class "Default")
      (node (ref "ELD") (pin "1") (pinfunction "A_1") (pintype "input"))
      (node (ref "EQ") (pin "1") (pinfunction "G_1") (pintype "unspecified"))
      (node (ref "ERG") (pin "2") (pinfunction "2_2") (pintype "input"))
      (node (ref "H5") (pin "11") (pinfunction "11_11") (pintype "unspecified"))
      (node (ref "J2") (pin "11") (pinfunction "D8/ICP_11") (pintype "unspecified"))
      (node (ref "OUT_8") (pin "1") (pinfunction "1_1") (pintype "unspecified"))
    )
    (net (code "25") (name "D9") (class "Default")
      (node (ref "FLD") (pin "1") (pinfunction "A_1") (pintype "input"))
      (node (ref "FQ") (pin "1") (pinfunction "G_1") (pintype "unspecified"))
      (node (ref "FRG") (pin "2") (pinfunction "2_2") (pintype "input"))
      (node (ref "H5") (pin "12") (pinfunction "12_12") (pintype "unspecified"))
      (node (ref "J2") (pin "12") (pinfunction "D9/0C1_12") (pintype "unspecified"))
      (node (ref "OUT_9") (pin "1") (pinfunction "1_1") (pintype "unspecified"))
    )
    (net (code "26") (name "D10") (class "Default")
      (node (ref "GLD") (pin "1") (pinfunction "A_1") (pintype "input"))
      (node (ref "GQ") (pin "1") (pinfunction "G_1") (pintype "unspecified"))
      (node (ref "GRG") (pin "2") (pinfunction "2_2") (pintype "input"))
      (node (ref "H5") (pin "13") (pinfunction "13_13") (pintype "unspecified"))
      (node (ref "J2") (pin "13") (pinfunction "D10_13") (pintype "unspecified"))
      (node (ref "OUT_10") (pin "1") (pinfunction "1_1") (pintype "unspecified"))
    )
    (net (code "27") (name "D11") (class "Default")
      (node (ref "H5") (pin "14") (pinfunction "14_14") (pintype "unspecified"))
      (node (ref "HLD") (pin "1") (pinfunction "A_1") (pintype "input"))
      (node (ref "HQ") (pin "1") (pinfunction "G_1") (pintype "unspecified"))
      (node (ref "HRG") (pin "2") (pinfunction "2_2") (pintype "input"))
      (node (ref "J2") (pin "14") (pinfunction "D11/MOSI_14") (pintype "unspecified"))
      (node (ref "OUT_11") (pin "1") (pinfunction "1_1") (pintype "unspecified"))
    )
    (net (code "28") (name "D13") (class "Default")
      (node (ref "H4") (pin "15") (pinfunction "15_15") (pintype "unspecified"))
      (node (ref "J2") (pin "16") (pinfunction "SCK/D13_16") (pintype "unspecified"))
    )
    (net (code "29") (name "GND") (class "Default")
      (node (ref "AQ") (pin "2") (pinfunction "S_2") (pintype "unspecified"))
      (node (ref "ARG") (pin "1") (pinfunction "1_1") (pintype "input"))
      (node (ref "ARL") (pin "1") (pinfunction "1_1") (pintype "input"))
      (node (ref "BQ") (pin "2") (pinfunction "S_2") (pintype "unspecified"))
      (node (ref "BRG") (pin "1") (pinfunction "1_1") (pintype "input"))
      (node (ref "BRL") (pin "1") (pinfunction "1_1") (pintype "input"))
      (node (ref "BUZZER1") (pin "2") (pinfunction "2_2") (pintype "unspecified"))
      (node (ref "C1") (pin "2") (pinfunction "2_2") (pintype "input"))
      (node (ref "C10") (pin "1") (pinfunction "1_1") (pintype "unspecified"))
      (node (ref "C11") (pin "1") (pinfunction "1_1") (pintype "unspecified"))
      (node (ref "C2") (pin "2") (pinfunction "2_2") (pintype "input"))
      (node (ref "CQ") (pin "2") (pinfunction "S_2") (pintype "unspecified"))
      (node (ref "CRG") (pin "1") (pinfunction "1_1") (pintype "input"))
      (node (ref "CRL") (pin "1") (pinfunction "1_1") (pintype "input"))
      (node (ref "DC1") (pin "2") (pinfunction "2_2") (pintype "unspecified"))
      (node (ref "DC1") (pin "3") (pinfunction "3_3") (pintype "unspecified"))
      (node (ref "DQ") (pin "2") (pinfunction "S_2") (pintype "unspecified"))
      (node (ref "DRG") (pin "1") (pinfunction "1_1") (pintype "input"))
      (node (ref "DRL") (pin "1") (pinfunction "1_1") (pintype "input"))
      (node (ref "EQ") (pin "2") (pinfunction "S_2") (pintype "unspecified"))
      (node (ref "ERG") (pin "1") (pinfunction "1_1") (pintype "input"))
      (node (ref "ERL") (pin "1") (pinfunction "1_1") (pintype "input"))
      (node (ref "FQ") (pin "2") (pinfunction "S_2") (pintype "unspecified"))
      (node (ref "FRG") (pin "1") (pinfunction "1_1") (pintype "input"))
      (node (ref "FRL") (pin "1") (pinfunction "1_1") (pintype "input"))
      (node (ref "GQ") (pin "2") (pinfunction "S_2") (pintype "unspecified"))
      (node (ref "GRG") (pin "1") (pinfunction "1_1") (pintype "input"))
      (node (ref "GRL") (pin "1") (pinfunction "1_1") (pintype "input"))
      (node (ref "H1") (pin "6") (pinfunction "6_6") (pintype "input"))
      (node (ref "H10") (pin "6") (pinfunction "6_6") (pintype "input"))
      (node (ref "H11") (pin "6") (pinfunction "6_6") (pintype "input"))
      (node (ref "H2") (pin "6") (pinfunction "6_6") (pintype "input"))
      (node (ref "H3") (pin "6") (pinfunction "6_6") (pintype "input"))
      (node (ref "H4") (pin "2") (pinfunction "2_2") (pintype "unspecified"))
      (node (ref "H5") (pin "4") (pinfunction "4_4") (pintype "unspecified"))
      (node (ref "H6") (pin "6") (pinfunction "6_6") (pintype "input"))
      (node (ref "H8") (pin "6") (pinfunction "6_6") (pintype "input"))
      (node (ref "H9") (pin "6") (pinfunction "6_6") (pintype "input"))
      (node (ref "HQ") (pin "2") (pinfunction "S_2") (pintype "unspecified"))
      (node (ref "HRG") (pin "1") (pinfunction "1_1") (pintype "input"))
      (node (ref "HRL") (pin "1") (pinfunction "1_1") (pintype "input"))
      (node (ref "J2") (pin "29") (pinfunction "GND_29") (pintype "unspecified"))
      (node (ref "J2") (pin "4") (pinfunction "GND_4") (pintype "unspecified"))
      (node (ref "OLED") (pin "2") (pinfunction "GND_2") (pintype "passive"))
      (node (ref "OUT_10") (pin "2") (pinfunction "2_2") (pintype "unspecified"))
      (node (ref "OUT_11") (pin "2") (pinfunction "2_2") (pintype "unspecified"))
      (node (ref "OUT_4") (pin "2") (pinfunction "2_2") (pintype "unspecified"))
      (node (ref "OUT_5") (pin "2") (pinfunction "2_2") (pintype "unspecified"))
      (node (ref "OUT_6") (pin "2") (pinfunction "2_2") (pintype "unspecified"))
      (node (ref "OUT_7") (pin "2") (pinfunction "2_2") (pintype "unspecified"))
      (node (ref "OUT_8") (pin "2") (pinfunction "2_2") (pintype "unspecified"))
      (node (ref "OUT_9") (pin "2") (pinfunction "2_2") (pintype "unspecified"))
      (node (ref "P2") (pin "1") (pinfunction "1_1") (pintype "input"))
      (node (ref "P3") (pin "1") (pinfunction "1_1") (pintype "input"))
      (node (ref "RL12V") (pin "2") (pinfunction "2_2") (pintype "input"))
      (node (ref "SENS_2") (pin "3") (pinfunction "3_3") (pintype "unspecified"))
      (node (ref "SENS_3") (pin "3") (pinfunction "3_3") (pintype "unspecified"))
      (node (ref "SENS_A0") (pin "3") (pinfunction "3_3") (pintype "unspecified"))
      (node (ref "SENS_A1") (pin "3") (pinfunction "3_3") (pintype "unspecified"))
      (node (ref "SENS_A2") (pin "3") (pinfunction "3_3") (pintype "unspecified"))
      (node (ref "SENS_A3") (pin "3") (pinfunction "3_3") (pintype "unspecified"))
      (node (ref "SW2") (pin "3") (pinfunction "3_3") (pintype "unspecified"))
      (node (ref "SW2") (pin "4") (pinfunction "4_4") (pintype "unspecified"))
      (node (ref "SW3") (pin "3") (pinfunction "3_3") (pintype "unspecified"))
      (node (ref "SW3") (pin "4") (pinfunction "4_4") (pintype "unspecified"))
      (node (ref "SWA0") (pin "3") (pinfunction "3_3") (pintype "unspecified"))
      (node (ref "SWA0") (pin "4") (pinfunction "4_4") (pintype "unspecified"))
      (node (ref "SWA1") (pin "3") (pinfunction "3_3") (pintype "unspecified"))
      (node (ref "SWA1") (pin "4") (pinfunction "4_4") (pintype "unspecified"))
      (node (ref "SWA2") (pin "3") (pinfunction "3_3") (pintype "unspecified"))
      (node (ref "SWA2") (pin "4") (pinfunction "4_4") (pintype "unspecified"))
      (node (ref "SWA3") (pin "3") (pinfunction "3_3") (pintype "unspecified"))
      (node (ref "SWA3") (pin "4") (pinfunction "4_4") (pintype "unspecified"))
      (node (ref "U3") (pin "3") (pinfunction "GND_3") (pintype "unspecified"))
      (node (ref "U5") (pin "2") (pinfunction "GND_2") (pintype "unspecified"))
    )
    (net (code "30") (name "Net-(ADM-A)") (class "Default")
      (node (ref "ACM") (pin "2") (pinfunction "2_2") (pintype "input"))
      (node (ref "ACON") (pin "2") (pinfunction "2_2") (pintype "unspecified"))
      (node (ref "ADM") (pin "2") (pinfunction "A_2") (pintype "unspecified"))
      (node (ref "AQ") (pin "3") (pinfunction "D_3") (pintype "unspecified"))
    )
    (net (code "31") (name "Net-(ADM-C)") (class "Default")
      (node (ref "ACM") (pin "1") (pinfunction "1_1") (pintype "input"))
      (node (ref "ACON") (pin "1") (pinfunction "1_1") (pintype "unspecified"))
      (node (ref "ADM") (pin "1") (pinfunction "C_1") (pintype "unspecified"))
      (node (ref "AJ12V") (pin "1") (pinfunction "1_1") (pintype "bidirectional"))
      (node (ref "AJ5V") (pin "1") (pinfunction "1_1") (pintype "bidirectional"))
      (node (ref "AJ9V") (pin "1") (pinfunction "1_1") (pintype "bidirectional"))
    )
    (net (code "32") (name "Net-(ALD-C)") (class "Default")
      (node (ref "ALD") (pin "2") (pinfunction "C_2") (pintype "input"))
      (node (ref "ARL") (pin "2") (pinfunction "2_2") (pintype "input"))
    )
    (net (code "33") (name "Net-(BDM-A)") (class "Default")
      (node (ref "BCM") (pin "2") (pinfunction "2_2") (pintype "input"))
      (node (ref "BCON") (pin "2") (pinfunction "2_2") (pintype "unspecified"))
      (node (ref "BDM") (pin "2") (pinfunction "A_2") (pintype "unspecified"))
      (node (ref "BQ") (pin "3") (pinfunction "D_3") (pintype "unspecified"))
    )
    (net (code "34") (name "Net-(BDM-C)") (class "Default")
      (node (ref "BCM") (pin "1") (pinfunction "1_1") (pintype "input"))
      (node (ref "BCON") (pin "1") (pinfunction "1_1") (pintype "unspecified"))
      (node (ref "BDM") (pin "1") (pinfunction "C_1") (pintype "unspecified"))
      (node (ref "BJ12V") (pin "1") (pinfunction "1_1") (pintype "bidirectional"))
      (node (ref "BJ5V") (pin "1") (pinfunction "1_1") (pintype "bidirectional"))
      (node (ref "BJ9V") (pin "1") (pinfunction "1_1") (pintype "bidirectional"))
    )
    (net (code "35") (name "Net-(BLD-C)") (class "Default")
      (node (ref "BLD") (pin "2") (pinfunction "C_2") (pintype "input"))
      (node (ref "BRL") (pin "2") (pinfunction "2_2") (pintype "input"))
    )
    (net (code "36") (name "Net-(CDM-A)") (class "Default")
      (node (ref "CCM") (pin "2") (pinfunction "2_2") (pintype "input"))
      (node (ref "CCON") (pin "2") (pinfunction "2_2") (pintype "unspecified"))
      (node (ref "CDM") (pin "2") (pinfunction "A_2") (pintype "unspecified"))
      (node (ref "CQ") (pin "3") (pinfunction "D_3") (pintype "unspecified"))
    )
    (net (code "37") (name "Net-(CDM-C)") (class "Default")
      (node (ref "CCM") (pin "1") (pinfunction "1_1") (pintype "input"))
      (node (ref "CCON") (pin "1") (pinfunction "1_1") (pintype "unspecified"))
      (node (ref "CDM") (pin "1") (pinfunction "C_1") (pintype "unspecified"))
      (node (ref "CJ12V") (pin "1") (pinfunction "1_1") (pintype "bidirectional"))
      (node (ref "CJ5V") (pin "1") (pinfunction "1_1") (pintype "bidirectional"))
      (node (ref "CJ9V") (pin "1") (pinfunction "1_1") (pintype "bidirectional"))
    )
    (net (code "38") (name "Net-(CLD-C)") (class "Default")
      (node (ref "CLD") (pin "2") (pinfunction "C_2") (pintype "input"))
      (node (ref "CRL") (pin "2") (pinfunction "2_2") (pintype "input"))
    )
    (net (code "39") (name "Net-(DDM-A)") (class "Default")
      (node (ref "DCM") (pin "2") (pinfunction "2_2") (pintype "input"))
      (node (ref "DCON") (pin "2") (pinfunction "2_2") (pintype "unspecified"))
      (node (ref "DDM") (pin "2") (pinfunction "A_2") (pintype "unspecified"))
      (node (ref "DQ") (pin "3") (pinfunction "D_3") (pintype "unspecified"))
    )
    (net (code "40") (name "Net-(DDM-C)") (class "Default")
      (node (ref "DCM") (pin "1") (pinfunction "1_1") (pintype "input"))
      (node (ref "DCON") (pin "1") (pinfunction "1_1") (pintype "unspecified"))
      (node (ref "DDM") (pin "1") (pinfunction "C_1") (pintype "unspecified"))
      (node (ref "DJ12V") (pin "1") (pinfunction "1_1") (pintype "bidirectional"))
      (node (ref "DJ5V") (pin "1") (pinfunction "1_1") (pintype "bidirectional"))
      (node (ref "DJ9V") (pin "1") (pinfunction "1_1") (pintype "bidirectional"))
    )
    (net (code "41") (name "Net-(DLD-C)") (class "Default")
      (node (ref "DLD") (pin "2") (pinfunction "C_2") (pintype "input"))
      (node (ref "DRL") (pin "2") (pinfunction "2_2") (pintype "input"))
    )
    (net (code "42") (name "Net-(EDM-A)") (class "Default")
      (node (ref "ECM") (pin "2") (pinfunction "2_2") (pintype "input"))
      (node (ref "ECON") (pin "2") (pinfunction "2_2") (pintype "unspecified"))
      (node (ref "EDM") (pin "2") (pinfunction "A_2") (pintype "unspecified"))
      (node (ref "EQ") (pin "3") (pinfunction "D_3") (pintype "unspecified"))
    )
    (net (code "43") (name "Net-(EDM-C)") (class "Default")
      (node (ref "ECM") (pin "1") (pinfunction "1_1") (pintype "input"))
      (node (ref "ECON") (pin "1") (pinfunction "1_1") (pintype "unspecified"))
      (node (ref "EDM") (pin "1") (pinfunction "C_1") (pintype "unspecified"))
      (node (ref "EJ12V") (pin "1") (pinfunction "1_1") (pintype "bidirectional"))
      (node (ref "EJ5V") (pin "1") (pinfunction "1_1") (pintype "bidirectional"))
      (node (ref "EJ9V") (pin "1") (pinfunction "1_1") (pintype "bidirectional"))
    )
    (net (code "44") (name "Net-(ELD-C)") (class "Default")
      (node (ref "ELD") (pin "2") (pinfunction "C_2") (pintype "input"))
      (node (ref "ERL") (pin "2") (pinfunction "2_2") (pintype "input"))
    )
    (net (code "45") (name "Net-(FDM-A)") (class "Default")
      (node (ref "FCM") (pin "2") (pinfunction "2_2") (pintype "input"))
      (node (ref "FCON") (pin "2") (pinfunction "2_2") (pintype "unspecified"))
      (node (ref "FDM") (pin "2") (pinfunction "A_2") (pintype "unspecified"))
      (node (ref "FQ") (pin "3") (pinfunction "D_3") (pintype "unspecified"))
    )
    (net (code "46") (name "Net-(FDM-C)") (class "Default")
      (node (ref "FCM") (pin "1") (pinfunction "1_1") (pintype "input"))
      (node (ref "FCON") (pin "1") (pinfunction "1_1") (pintype "unspecified"))
      (node (ref "FDM") (pin "1") (pinfunction "C_1") (pintype "unspecified"))
      (node (ref "FJ12V") (pin "1") (pinfunction "1_1") (pintype "bidirectional"))
      (node (ref "FJ5V") (pin "1") (pinfunction "1_1") (pintype "bidirectional"))
      (node (ref "FJ9V") (pin "1") (pinfunction "1_1") (pintype "bidirectional"))
    )
    (net (code "47") (name "Net-(FLD-C)") (class "Default")
      (node (ref "FLD") (pin "2") (pinfunction "C_2") (pintype "input"))
      (node (ref "FRL") (pin "2") (pinfunction "2_2") (pintype "input"))
    )
    (net (code "48") (name "Net-(GDM-A)") (class "Default")
      (node (ref "GCM") (pin "2") (pinfunction "2_2") (pintype "input"))
      (node (ref "GCON") (pin "2") (pinfunction "2_2") (pintype "unspecified"))
      (node (ref "GDM") (pin "2") (pinfunction "A_2") (pintype "unspecified"))
      (node (ref "GQ") (pin "3") (pinfunction "D_3") (pintype "unspecified"))
    )
    (net (code "49") (name "Net-(GDM-C)") (class "Default")
      (node (ref "GCM") (pin "1") (pinfunction "1_1") (pintype "input"))
      (node (ref "GCON") (pin "1") (pinfunction "1_1") (pintype "unspecified"))
      (node (ref "GDM") (pin "1") (pinfunction "C_1") (pintype "unspecified"))
      (node (ref "GJ12V") (pin "1") (pinfunction "1_1") (pintype "bidirectional"))
      (node (ref "GJ5V") (pin "1") (pinfunction "1_1") (pintype "bidirectional"))
      (node (ref "GJ9V") (pin "1") (pinfunction "1_1") (pintype "bidirectional"))
    )
    (net (code "50") (name "Net-(GLD-C)") (class "Default")
      (node (ref "GLD") (pin "2") (pinfunction "C_2") (pintype "input"))
      (node (ref "GRL") (pin "2") (pinfunction "2_2") (pintype "input"))
    )
    (net (code "51") (name "Net-(H4-Pad3)") (class "Default")
      (node (ref "H4") (pin "3") (pinfunction "3_3") (pintype "unspecified"))
      (node (ref "J2") (pin "28") (pinfunction "RESET_28") (pintype "unspecified"))
    )
    (net (code "52") (name "Net-(H5-Pad3)") (class "Default")
      (node (ref "H5") (pin "3") (pinfunction "3_3") (pintype "unspecified"))
      (node (ref "J2") (pin "3") (pinfunction "RESET_3") (pintype "unspecified"))
    )
    (net (code "53") (name "Net-(HDM-A)") (class "Default")
      (node (ref "HCM") (pin "2") (pinfunction "2_2") (pintype "input"))
      (node (ref "HCON") (pin "2") (pinfunction "2_2") (pintype "unspecified"))
      (node (ref "HDM") (pin "2") (pinfunction "A_2") (pintype "unspecified"))
      (node (ref "HQ") (pin "3") (pinfunction "D_3") (pintype "unspecified"))
    )
    (net (code "54") (name "Net-(HDM-C)") (class "Default")
      (node (ref "HCM") (pin "1") (pinfunction "1_1") (pintype "input"))
      (node (ref "HCON") (pin "1") (pinfunction "1_1") (pintype "unspecified"))
      (node (ref "HDM") (pin "1") (pinfunction "C_1") (pintype "unspecified"))
      (node (ref "HJ12V") (pin "1") (pinfunction "1_1") (pintype "bidirectional"))
      (node (ref "HJ5V") (pin "1") (pinfunction "1_1") (pintype "bidirectional"))
      (node (ref "HJ9V") (pin "1") (pinfunction "1_1") (pintype "bidirectional"))
    )
    (net (code "55") (name "Net-(HLD-C)") (class "Default")
      (node (ref "HLD") (pin "2") (pinfunction "C_2") (pintype "input"))
      (node (ref "HRL") (pin "2") (pinfunction "2_2") (pintype "input"))
    )
    (net (code "56") (name "Net-(J2-AREF)") (class "Default")
      (node (ref "H4") (pin "13") (pinfunction "13_13") (pintype "unspecified"))
      (node (ref "J2") (pin "18") (pinfunction "AREF_18") (pintype "unspecified"))
    )
    (net (code "57") (name "Net-(L12V-C)") (class "Default")
      (node (ref "L12V") (pin "2") (pinfunction "C_2") (pintype "input"))
      (node (ref "RL12V") (pin "1") (pinfunction "1_1") (pintype "input"))
    )
    (net (code "58") (name "Net-(U3-EN)") (class "Default")
      (node (ref "R1") (pin "1") (pinfunction "1_1") (pintype "input"))
      (node (ref "U3") (pin "1") (pinfunction "EN_1") (pintype "unspecified"))
    )
    (net (code "60") (name "unconnected-(H1-Pad2)") (class "Default")
      (node (ref "H1") (pin "2") (pinfunction "2_2") (pintype "input"))
    )
    (net (code "61") (name "unconnected-(H1-Pad3)") (class "Default")
      (node (ref "H1") (pin "3") (pinfunction "3_3") (pintype "input"))
    )
    (net (code "62") (name "unconnected-(H1-Pad4)") (class "Default")
      (node (ref "H1") (pin "4") (pinfunction "4_4") (pintype "input"))
    )
    (net (code "63") (name "unconnected-(H1-Pad5)") (class "Default")
      (node (ref "H1") (pin "5") (pinfunction "5_5") (pintype "input"))
    )
    (net (code "64") (name "unconnected-(H2-Pad2)") (class "Default")
      (node (ref "H2") (pin "2") (pinfunction "2_2") (pintype "input"))
    )
    (net (code "65") (name "unconnected-(H2-Pad3)") (class "Default")
      (node (ref "H2") (pin "3") (pinfunction "3_3") (pintype "input"))
    )
    (net (code "66") (name "unconnected-(H2-Pad4)") (class "Default")
      (node (ref "H2") (pin "4") (pinfunction "4_4") (pintype "input"))
    )
    (net (code "67") (name "unconnected-(H2-Pad5)") (class "Default")
      (node (ref "H2") (pin "5") (pinfunction "5_5") (pintype "input"))
    )
    (net (code "68") (name "unconnected-(H3-Pad2)") (class "Default")
      (node (ref "H3") (pin "2") (pinfunction "2_2") (pintype "input"))
    )
    (net (code "69") (name "unconnected-(H3-Pad3)") (class "Default")
      (node (ref "H3") (pin "3") (pinfunction "3_3") (pintype "input"))
    )
    (net (code "70") (name "unconnected-(H3-Pad4)") (class "Default")
      (node (ref "H3") (pin "4") (pinfunction "4_4") (pintype "input"))
    )
    (net (code "71") (name "unconnected-(H3-Pad5)") (class "Default")
      (node (ref "H3") (pin "5") (pinfunction "5_5") (pintype "input"))
    )
    (net (code "72") (name "unconnected-(H6-Pad2)") (class "Default")
      (node (ref "H6") (pin "2") (pinfunction "2_2") (pintype "input"))
    )
    (net (code "73") (name "unconnected-(H6-Pad3)") (class "Default")
      (node (ref "H6") (pin "3") (pinfunction "3_3") (pintype "input"))
    )
    (net (code "74") (name "unconnected-(H6-Pad4)") (class "Default")
      (node (ref "H6") (pin "4") (pinfunction "4_4") (pintype "input"))
    )
    (net (code "75") (name "unconnected-(H6-Pad5)") (class "Default")
      (node (ref "H6") (pin "5") (pinfunction "5_5") (pintype "input"))
    )
    (net (code "76") (name "unconnected-(H8-Pad2)") (class "Default")
      (node (ref "H8") (pin "2") (pinfunction "2_2") (pintype "input"))
    )
    (net (code "77") (name "unconnected-(H8-Pad3)") (class "Default")
      (node (ref "H8") (pin "3") (pinfunction "3_3") (pintype "input"))
    )
    (net (code "78") (name "unconnected-(H8-Pad4)") (class "Default")
      (node (ref "H8") (pin "4") (pinfunction "4_4") (pintype "input"))
    )
    (net (code "79") (name "unconnected-(H8-Pad5)") (class "Default")
      (node (ref "H8") (pin "5") (pinfunction "5_5") (pintype "input"))
    )
    (net (code "80") (name "unconnected-(H9-Pad2)") (class "Default")
      (node (ref "H9") (pin "2") (pinfunction "2_2") (pintype "input"))
    )
    (net (code "81") (name "unconnected-(H9-Pad3)") (class "Default")
      (node (ref "H9") (pin "3") (pinfunction "3_3") (pintype "input"))
    )
    (net (code "82") (name "unconnected-(H9-Pad4)") (class "Default")
      (node (ref "H9") (pin "4") (pinfunction "4_4") (pintype "input"))
    )
    (net (code "83") (name "unconnected-(H9-Pad5)") (class "Default")
      (node (ref "H9") (pin "5") (pinfunction "5_5") (pintype "input"))
    )
    (net (code "84") (name "unconnected-(H10-Pad2)") (class "Default")
      (node (ref "H10") (pin "2") (pinfunction "2_2") (pintype "input"))
    )
    (net (code "85") (name "unconnected-(H10-Pad3)") (class "Default")
      (node (ref "H10") (pin "3") (pinfunction "3_3") (pintype "input"))
    )
    (net (code "86") (name "unconnected-(H10-Pad4)") (class "Default")
      (node (ref "H10") (pin "4") (pinfunction "4_4") (pintype "input"))
    )
    (net (code "87") (name "unconnected-(H10-Pad5)") (class "Default")
      (node (ref "H10") (pin "5") (pinfunction "5_5") (pintype "input"))
    )
    (net (code "88") (name "unconnected-(H11-Pad2)") (class "Default")
      (node (ref "H11") (pin "2") (pinfunction "2_2") (pintype "input"))
    )
    (net (code "89") (name "unconnected-(H11-Pad3)") (class "Default")
      (node (ref "H11") (pin "3") (pinfunction "3_3") (pintype "input"))
    )
    (net (code "90") (name "unconnected-(H11-Pad4)") (class "Default")
      (node (ref "H11") (pin "4") (pinfunction "4_4") (pintype "input"))
    )
    (net (code "91") (name "unconnected-(H11-Pad5)") (class "Default")
      (node (ref "H11") (pin "5") (pinfunction "5_5") (pintype "input"))
    )
    (net (code "92") (name "unconnected-(P2-Pad4)") (class "Default")
      (node (ref "P2") (pin "4") (pinfunction "4_4") (pintype "input"))
    )
    (net (code "93") (name "unconnected-(P2-Pad5)") (class "Default")
      (node (ref "P2") (pin "5") (pinfunction "5_5") (pintype "input"))
    )
    (net (code "94") (name "unconnected-(P3-Pad4)") (class "Default")
      (node (ref "P3") (pin "4") (pinfunction "4_4") (pintype "input"))
    )
    (net (code "95") (name "unconnected-(P3-Pad5)") (class "Default")
      (node (ref "P3") (pin "5") (pinfunction "5_5") (pintype "input"))
    )
  )
)
